# CTRL_IF.net
KiCad netlist of a schematic drawn in Altium Designer
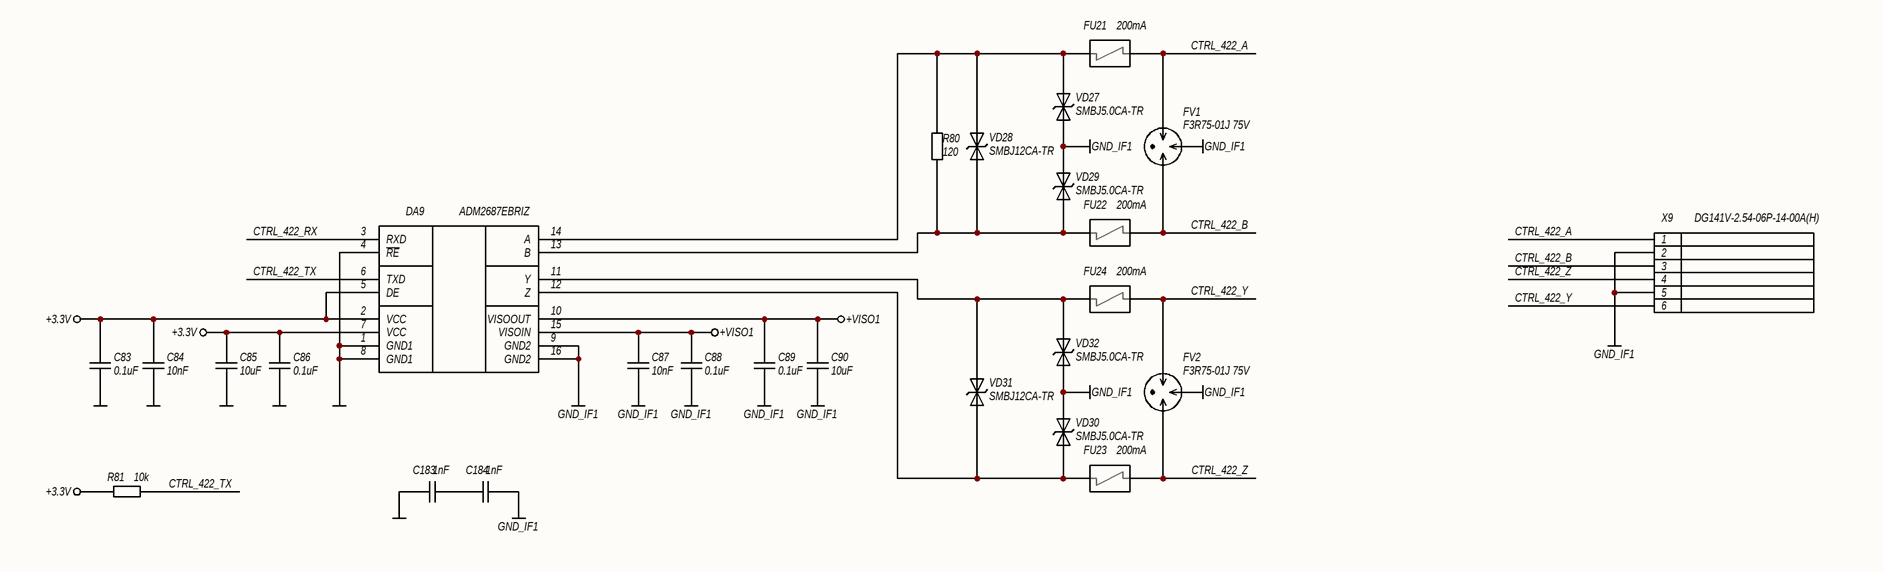
[diagram p0: CTRL_IF.SchDoc]

(export (version "E")
  (design (tool "Eeschema 10.0.6"))
  (components
    (comp (ref "C83")
      (value "0.1uF")
      (footprint "C0603N")
      (description "Конденсатор")
      (libsource (lib "Components Library") (part "CAP_FIXED"))
    )
    (comp (ref "C84")
      (value "10nF")
      (footprint "C0603N")
      (description "Конденсатор")
      (libsource (lib "Components Library") (part "CAP_FIXED"))
    )
    (comp (ref "C85")
      (value "10uF")
      (footprint "C0805N")
      (description "Конденсатор")
      (libsource (lib "Components Library") (part "CAP_FIXED"))
    )
    (comp (ref "C86")
      (value "0.1uF")
      (footprint "C0603N")
      (description "Конденсатор")
      (libsource (lib "Components Library") (part "CAP_FIXED"))
    )
    (comp (ref "C87")
      (value "10nF")
      (footprint "C0603N")
      (description "Конденсатор")
      (libsource (lib "Components Library") (part "CAP_FIXED"))
    )
    (comp (ref "C88")
      (value "0.1uF")
      (footprint "C0603N")
      (description "Конденсатор")
      (libsource (lib "Components Library") (part "CAP_FIXED"))
    )
    (comp (ref "C89")
      (value "0.1uF")
      (footprint "C0603N")
      (description "Конденсатор")
      (libsource (lib "Components Library") (part "CAP_FIXED"))
    )
    (comp (ref "C90")
      (value "10uF")
      (footprint "C0805N")
      (description "Конденсатор")
      (libsource (lib "Components Library") (part "CAP_FIXED"))
    )
    (comp (ref "C183")
      (value "1nF")
      (footprint "C1808N")
      (description "Конденсатор")
      (libsource (lib "Components Library") (part "CAP_FIXED"))
    )
    (comp (ref "C184")
      (value "1nF")
      (footprint "C1808N")
      (description "Конденсатор")
      (libsource (lib "Components Library") (part "CAP_FIXED"))
    )
    (comp (ref "DA9")
      (value "ADM2687EBRIZ")
      (footprint "SOIC16_IC")
      (description "Микросхема интерфейса RS485")
      (libsource (lib "Components Library") (part "ADM2687E"))
    )
    (comp (ref "FU21")
      (value "200mA")
      (footprint "TBU-CA")
      (description "Полупроводниковый предохранитель")
      (libsource (lib "Components Library") (part "FUSE_TBU"))
    )
    (comp (ref "FU22")
      (value "200mA")
      (footprint "TBU-CA")
      (description "Полупроводниковый предохранитель")
      (libsource (lib "Components Library") (part "FUSE_TBU"))
    )
    (comp (ref "FU23")
      (value "200mA")
      (footprint "TBU-CA")
      (description "Полупроводниковый предохранитель")
      (libsource (lib "Components Library") (part "FUSE_TBU"))
    )
    (comp (ref "FU24")
      (value "200mA")
      (footprint "TBU-CA")
      (description "Полупроводниковый предохранитель")
      (libsource (lib "Components Library") (part "FUSE_TBU"))
    )
    (comp (ref "FV1")
      (value "F3R75-01J 75V")
      (footprint "GDT_3PIN_B2")
      (description "Газовый разрядник, трехвыводный")
      (libsource (lib "Components Library") (part "GDT_3PIN"))
    )
    (comp (ref "FV2")
      (value "F3R75-01J 75V")
      (footprint "GDT_3PIN_B2")
      (description "Газовый разрядник, трехвыводный")
      (libsource (lib "Components Library") (part "GDT_3PIN"))
    )
    (comp (ref "R80")
      (value "120")
      (footprint "R0805N")
      (description "Резистор")
      (libsource (lib "Components Library") (part "RES_FIXED"))
    )
    (comp (ref "R81")
      (value "10k")
      (footprint "R0603N")
      (description "Резистор")
      (libsource (lib "") (part "RES_FIXED_1"))
    )
    (comp (ref "VD27")
      (value "SMBJ5.0CA-TR")
      (footprint "SMB")
      (description "TVS диод двунаправленный")
      (libsource (lib "Components Library") (part "TVS_BIDIR"))
    )
    (comp (ref "VD28")
      (value "SMBJ12CA-TR")
      (footprint "SMB")
      (description "TVS диод двунаправленный")
      (libsource (lib "Components Library") (part "TVS_BIDIR"))
    )
    (comp (ref "VD29")
      (value "SMBJ5.0CA-TR")
      (footprint "SMB")
      (description "TVS диод двунаправленный")
      (libsource (lib "Components Library") (part "TVS_BIDIR"))
    )
    (comp (ref "VD30")
      (value "SMBJ5.0CA-TR")
      (footprint "SMB")
      (description "TVS диод двунаправленный")
      (libsource (lib "Components Library") (part "TVS_BIDIR"))
    )
    (comp (ref "VD31")
      (value "SMBJ12CA-TR")
      (footprint "SMB")
      (description "TVS диод двунаправленный")
      (libsource (lib "Components Library") (part "TVS_BIDIR"))
    )
    (comp (ref "VD32")
      (value "SMBJ5.0CA-TR")
      (footprint "SMB")
      (description "TVS диод двунаправленный")
      (libsource (lib "Components Library") (part "TVS_BIDIR"))
    )
    (comp (ref "X9")
      (value "DG141V-2.54-06P-14-00A(H)")
      (footprint "DG141V-2.54-06P-14-00A(H)")
      (description "Разъем, 6 контактов")
      (libsource (lib "Components Library") (part "Connector 6"))
    )
  )
  (nets
    (net (code "1") (name "+3.3V") (class "Default")
      (node (ref "C83") (pin "2") (pinfunction "2_2") (pintype "passive"))
      (node (ref "C84") (pin "1") (pinfunction "1_1") (pintype "passive"))
      (node (ref "C85") (pin "2") (pinfunction "2_2") (pintype "passive"))
      (node (ref "C86") (pin "2") (pinfunction "2_2") (pintype "passive"))
      (node (ref "DA9") (pin "2") (pinfunction "VCC_2") (pintype "power_in"))
      (node (ref "DA9") (pin "5") (pinfunction "DE_5") (pintype "power_in"))
      (node (ref "DA9") (pin "7") (pinfunction "VCC_7") (pintype "power_in"))
      (node (ref "R81") (pin "2") (pinfunction "2_2") (pintype "passive"))
    )
    (net (code "2") (name "+VISO1") (class "Default")
      (node (ref "C87") (pin "1") (pinfunction "1_1") (pintype "passive"))
      (node (ref "C88") (pin "2") (pinfunction "2_2") (pintype "passive"))
      (node (ref "C89") (pin "2") (pinfunction "2_2") (pintype "passive"))
      (node (ref "C90") (pin "2") (pinfunction "2_2") (pintype "passive"))
      (node (ref "DA9") (pin "10") (pinfunction "VISOOUT_10") (pintype "power_in"))
      (node (ref "DA9") (pin "15") (pinfunction "VISOIN_15") (pintype "power_in"))
    )
    (net (code "3") (name "/CTRL_422_A") (class "Default")
      (node (ref "FU21") (pin "3") (pinfunction "IN/OUT_3") (pintype "passive"))
      (node (ref "FV1") (pin "1") (pinfunction "1_1") (pintype "passive"))
      (node (ref "X9") (pin "1") (pinfunction "1_1") (pintype "power_in"))
    )
    (net (code "4") (name "/CTRL_422_B") (class "Default")
      (node (ref "FU22") (pin "3") (pinfunction "IN/OUT_3") (pintype "passive"))
      (node (ref "FV1") (pin "3") (pinfunction "3_3") (pintype "passive"))
      (node (ref "X9") (pin "3") (pinfunction "3_3") (pintype "power_in"))
    )
    (net (code "5") (name "/CTRL_422_RX") (class "Default")
      (node (ref "DA9") (pin "3") (pinfunction "RXD_3") (pintype "power_in"))
    )
    (net (code "6") (name "/CTRL_422_TX") (class "Default")
      (node (ref "DA9") (pin "6") (pinfunction "TXD_6") (pintype "power_in"))
      (node (ref "R81") (pin "1") (pinfunction "1_1") (pintype "passive"))
    )
    (net (code "7") (name "/CTRL_422_Y") (class "Default")
      (node (ref "FU24") (pin "3") (pinfunction "IN/OUT_3") (pintype "passive"))
      (node (ref "FV2") (pin "3") (pinfunction "3_3") (pintype "passive"))
      (node (ref "X9") (pin "6") (pinfunction "6_6") (pintype "power_in"))
    )
    (net (code "8") (name "/CTRL_422_Z") (class "Default")
      (node (ref "FU23") (pin "3") (pinfunction "IN/OUT_3") (pintype "passive"))
      (node (ref "FV2") (pin "1") (pinfunction "1_1") (pintype "passive"))
      (node (ref "X9") (pin "4") (pinfunction "4_4") (pintype "power_in"))
    )
    (net (code "9") (name "GND") (class "Default")
      (node (ref "C183") (pin "2") (pinfunction "2_2") (pintype "passive"))
      (node (ref "C83") (pin "1") (pinfunction "1_1") (pintype "passive"))
      (node (ref "C84") (pin "2") (pinfunction "2_2") (pintype "passive"))
      (node (ref "C85") (pin "1") (pinfunction "1_1") (pintype "passive"))
      (node (ref "C86") (pin "1") (pinfunction "1_1") (pintype "passive"))
      (node (ref "DA9") (pin "1") (pinfunction "GND1_1") (pintype "power_in"))
      (node (ref "DA9") (pin "4") (pinfunction "~{RE}_4") (pintype "power_in"))
      (node (ref "DA9") (pin "8") (pinfunction "GND1_8") (pintype "power_in"))
    )
    (net (code "10") (name "GND_IF1") (class "Default")
      (node (ref "C184") (pin "1") (pinfunction "1_1") (pintype "passive"))
      (node (ref "C87") (pin "2") (pinfunction "2_2") (pintype "passive"))
      (node (ref "C88") (pin "1") (pinfunction "1_1") (pintype "passive"))
      (node (ref "C89") (pin "1") (pinfunction "1_1") (pintype "passive"))
      (node (ref "C90") (pin "1") (pinfunction "1_1") (pintype "passive"))
      (node (ref "DA9") (pin "16") (pinfunction "GND2_16") (pintype "power_in"))
      (node (ref "DA9") (pin "9") (pinfunction "GND2_9") (pintype "power_in"))
      (node (ref "FV1") (pin "2") (pinfunction "2_2") (pintype "passive"))
      (node (ref "FV2") (pin "2") (pinfunction "2_2") (pintype "passive"))
      (node (ref "VD27") (pin "2") (pinfunction "A2_2") (pintype "passive"))
      (node (ref "VD29") (pin "2") (pinfunction "A2_2") (pintype "passive"))
      (node (ref "VD30") (pin "2") (pinfunction "A2_2") (pintype "passive"))
      (node (ref "VD32") (pin "2") (pinfunction "A2_2") (pintype "passive"))
      (node (ref "X9") (pin "2") (pinfunction "2_2") (pintype "power_in"))
      (node (ref "X9") (pin "5") (pinfunction "5_5") (pintype "power_in"))
    )
    (net (code "11") (name "Net-(C183-Pad1)") (class "Default")
      (node (ref "C183") (pin "1") (pinfunction "1_1") (pintype "passive"))
      (node (ref "C184") (pin "2") (pinfunction "2_2") (pintype "passive"))
    )
    (net (code "12") (name "Net-(DA9-A)") (class "Default")
      (node (ref "DA9") (pin "14") (pinfunction "A_14") (pintype "power_in"))
      (node (ref "FU21") (pin "1") (pinfunction "IN/OUT_1") (pintype "passive"))
      (node (ref "R80") (pin "1") (pinfunction "1_1") (pintype "passive"))
      (node (ref "VD27") (pin "1") (pinfunction "A1_1") (pintype "passive"))
      (node (ref "VD28") (pin "1") (pinfunction "A1_1") (pintype "passive"))
    )
    (net (code "13") (name "Net-(DA9-B)") (class "Default")
      (node (ref "DA9") (pin "13") (pinfunction "B_13") (pintype "power_in"))
      (node (ref "FU22") (pin "1") (pinfunction "IN/OUT_1") (pintype "passive"))
      (node (ref "R80") (pin "2") (pinfunction "2_2") (pintype "passive"))
      (node (ref "VD28") (pin "2") (pinfunction "A2_2") (pintype "passive"))
      (node (ref "VD29") (pin "1") (pinfunction "A1_1") (pintype "passive"))
    )
    (net (code "14") (name "Net-(DA9-Y)") (class "Default")
      (node (ref "DA9") (pin "11") (pinfunction "Y_11") (pintype "power_in"))
      (node (ref "FU24") (pin "1") (pinfunction "IN/OUT_1") (pintype "passive"))
      (node (ref "VD31") (pin "2") (pinfunction "A2_2") (pintype "passive"))
      (node (ref "VD32") (pin "1") (pinfunction "A1_1") (pintype "passive"))
    )
    (net (code "15") (name "Net-(DA9-Z)") (class "Default")
      (node (ref "DA9") (pin "12") (pinfunction "Z_12") (pintype "power_in"))
      (node (ref "FU23") (pin "1") (pinfunction "IN/OUT_1") (pintype "passive"))
      (node (ref "VD30") (pin "1") (pinfunction "A1_1") (pintype "passive"))
      (node (ref "VD31") (pin "1") (pinfunction "A1_1") (pintype "passive"))
    )
  )
)
